# tester_V1_1.net
KiCad netlist of a schematic drawn in EAGLE
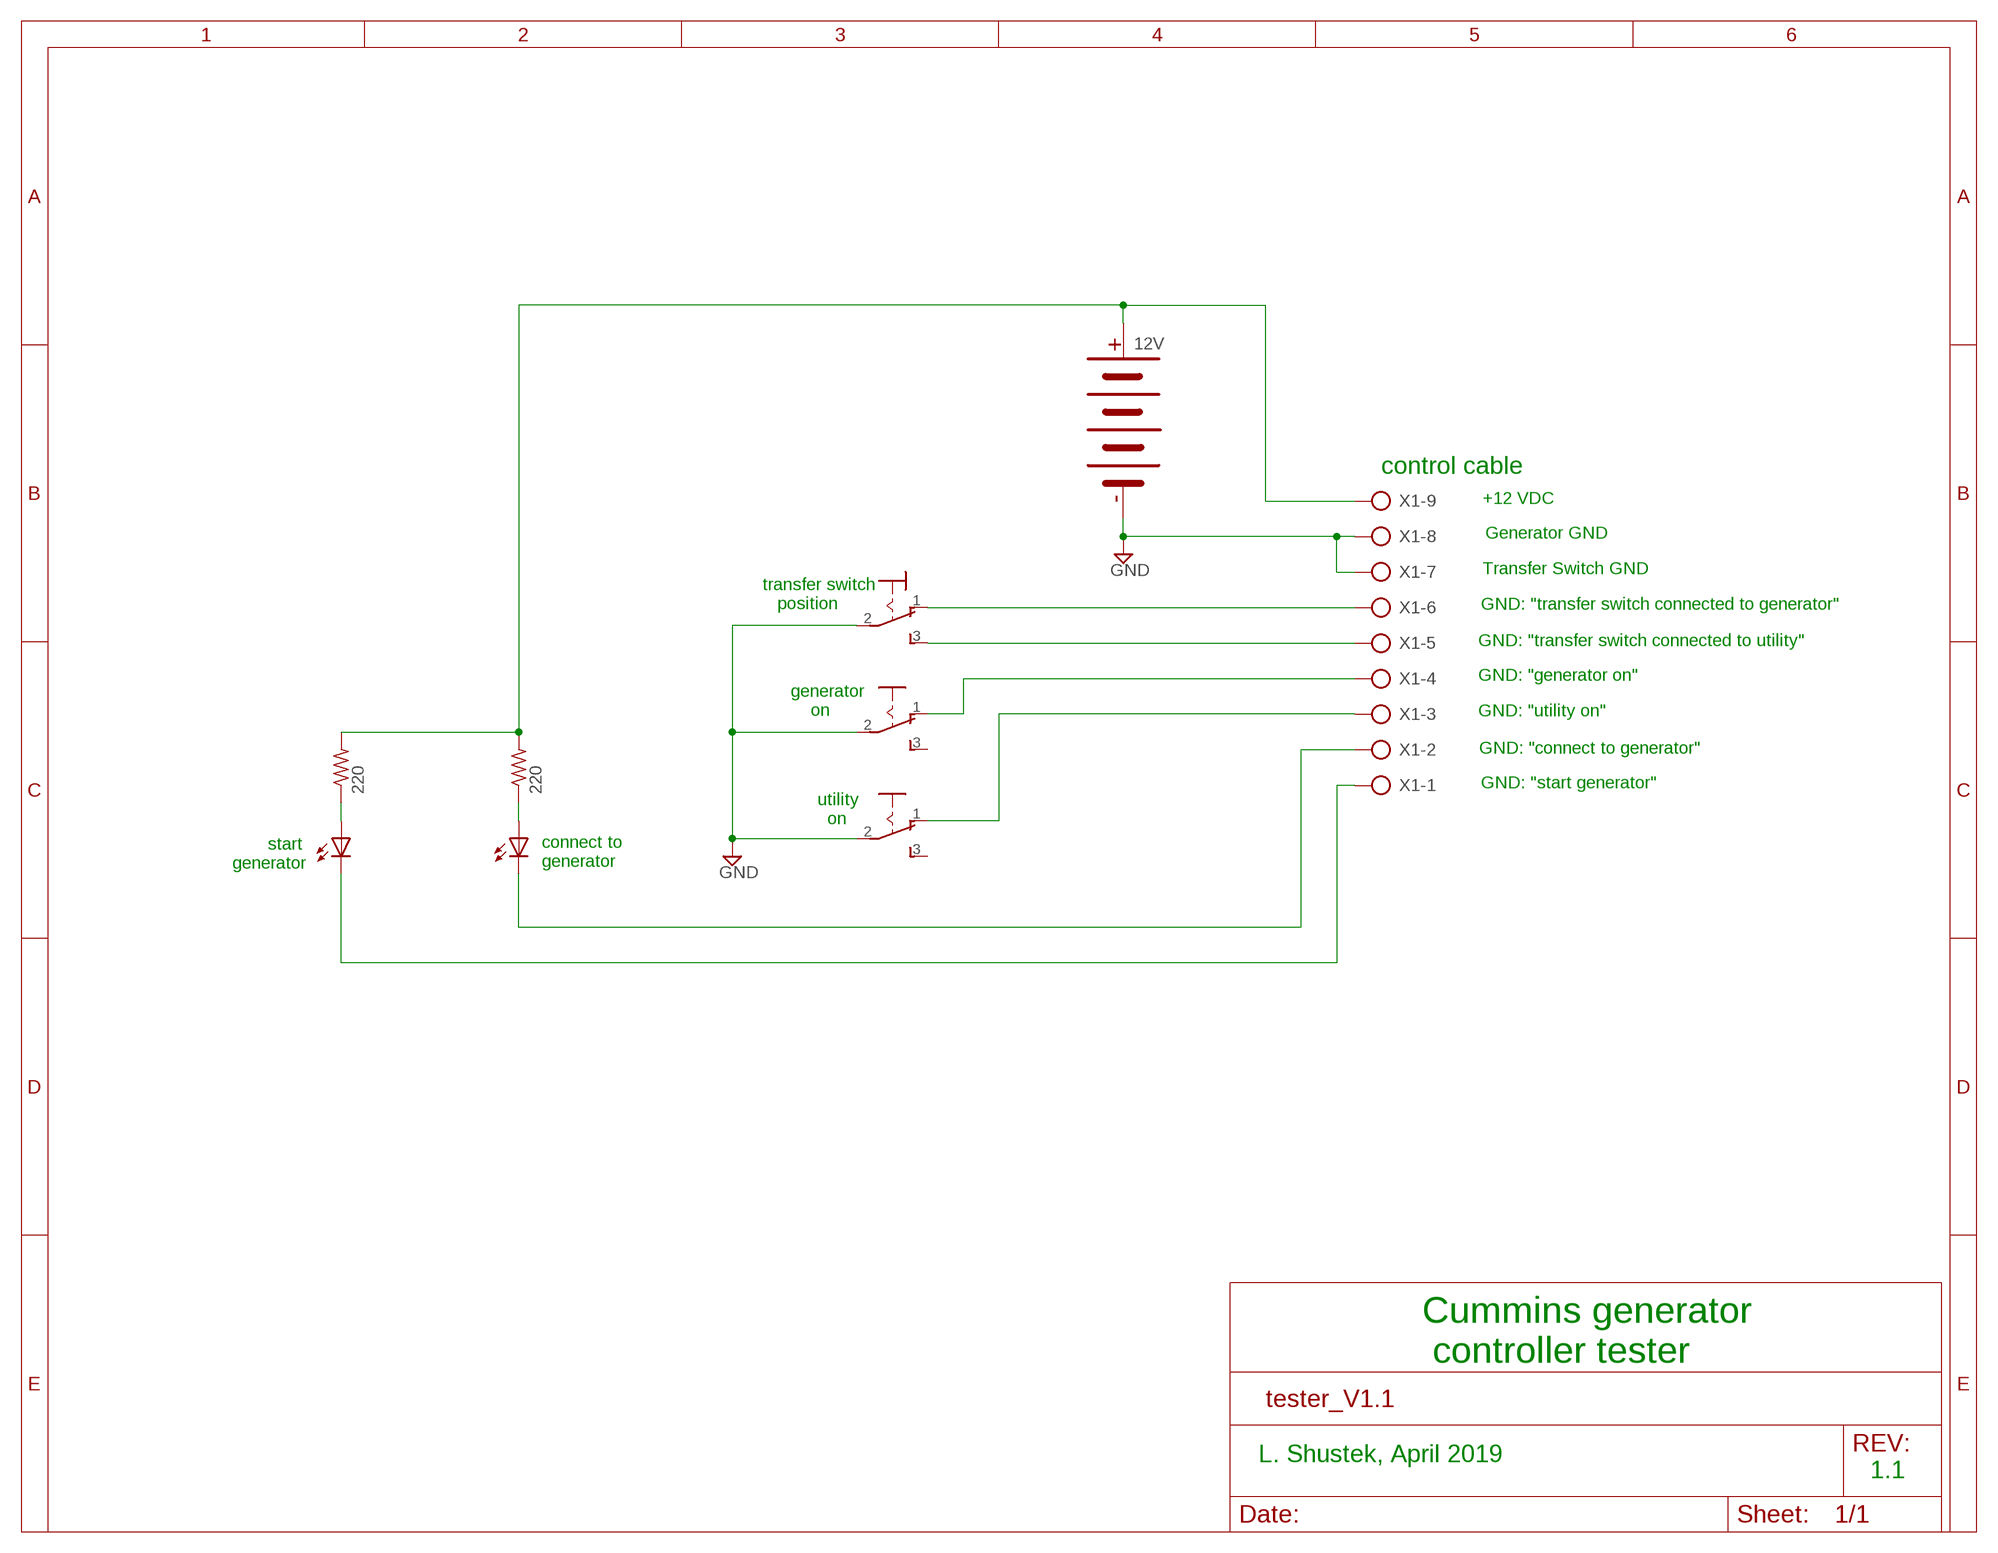
[diagram p0: schematic, sheet 1]

(export (version "E")
  (design (tool "Eeschema 10.0.6"))
  (components
    (comp (ref "LED1")
      (value "LED")
      (footprint "eagle-import:SMARTLED-TTW")
      (libsource (lib "eagle-import") (part "LED"))
    )
    (comp (ref "LED2")
      (value "LED")
      (footprint "eagle-import:SMARTLED-TTW")
      (libsource (lib "eagle-import") (part "LED"))
    )
    (comp (ref "R1")
      (value "220")
      (footprint "eagle-import:0204_5")
      (libsource (lib "eagle-import") (part "R-US_0204/5"))
    )
    (comp (ref "R2")
      (value "220")
      (footprint "eagle-import:0204_5")
      (libsource (lib "eagle-import") (part "R-US_0204/5"))
    )
    (comp (ref "S1")
      (value "320-916")
      (footprint "eagle-import:320-916")
      (libsource (lib "eagle-import") (part "320-916"))
    )
    (comp (ref "S2")
      (value "255SB")
      (footprint "eagle-import:255SB")
      (libsource (lib "eagle-import") (part "255SB"))
    )
    (comp (ref "S3")
      (value "255SB")
      (footprint "eagle-import:255SB")
      (libsource (lib "eagle-import") (part "255SB"))
    )
    (comp (ref "U$1")
      (value "12V")
      (footprint "eagle-import:4-CELL-BATTERY")
      (libsource (lib "eagle-import") (part "4-CELL-BATTERY"))
    )
    (comp (ref "X1")
      (value "AK500/9")
      (footprint "eagle-import:AK500_9")
      (libsource (lib "eagle-import") (part "AK500/9"))
    )
  )
  (nets
    (net (code "1") (name "GND") (class "Default")
      (node (ref "S1") (pin "2") (pinfunction "P_2") (pintype "passive"))
      (node (ref "S2") (pin "2") (pinfunction "P_2") (pintype "passive"))
      (node (ref "S3") (pin "2") (pinfunction "P_2") (pintype "passive"))
      (node (ref "U$1") (pin "P$1") (pinfunction "P$1_P$1") (pintype "bidirectional"))
      (node (ref "X1") (pin "7") (pinfunction "KL_7") (pintype "passive"))
      (node (ref "X1") (pin "8") (pinfunction "KL_8") (pintype "passive"))
    )
    (net (code "2") (name "Net-(LED1-A)") (class "Default")
      (node (ref "LED1") (pin "A@1") (pinfunction "A_A@1") (pintype "passive"))
      (node (ref "R1") (pin "1") (pinfunction "1_1") (pintype "passive"))
    )
    (net (code "3") (name "Net-(LED1-C)") (class "Default")
      (node (ref "LED1") (pin "C@1") (pinfunction "C_C@1") (pintype "passive"))
      (node (ref "X1") (pin "1") (pinfunction "KL_1") (pintype "passive"))
    )
    (net (code "4") (name "Net-(LED2-A)") (class "Default")
      (node (ref "LED2") (pin "A@1") (pinfunction "A_A@1") (pintype "passive"))
      (node (ref "R2") (pin "1") (pinfunction "1_1") (pintype "passive"))
    )
    (net (code "5") (name "Net-(LED2-C)") (class "Default")
      (node (ref "LED2") (pin "C@1") (pinfunction "C_C@1") (pintype "passive"))
      (node (ref "X1") (pin "2") (pinfunction "KL_2") (pintype "passive"))
    )
    (net (code "6") (name "Net-(S1-O)") (class "Default")
      (node (ref "S1") (pin "1") (pinfunction "O_1") (pintype "passive"))
      (node (ref "X1") (pin "6") (pinfunction "KL_6") (pintype "passive"))
    )
    (net (code "7") (name "Net-(S1-S)") (class "Default")
      (node (ref "S1") (pin "3") (pinfunction "S_3") (pintype "passive"))
      (node (ref "X1") (pin "5") (pinfunction "KL_5") (pintype "passive"))
    )
    (net (code "8") (name "Net-(S2-O)") (class "Default")
      (node (ref "S2") (pin "1") (pinfunction "O_1") (pintype "passive"))
      (node (ref "X1") (pin "4") (pinfunction "KL_4") (pintype "passive"))
    )
    (net (code "9") (name "Net-(S3-O)") (class "Default")
      (node (ref "S3") (pin "1") (pinfunction "O_1") (pintype "passive"))
      (node (ref "X1") (pin "3") (pinfunction "KL_3") (pintype "passive"))
    )
    (net (code "10") (name "Net-(X1I-KL)") (class "Default")
      (node (ref "R1") (pin "2") (pinfunction "2_2") (pintype "passive"))
      (node (ref "R2") (pin "2") (pinfunction "2_2") (pintype "passive"))
      (node (ref "U$1") (pin "P$2") (pinfunction "P$2_P$2") (pintype "bidirectional"))
      (node (ref "X1") (pin "9") (pinfunction "KL_9") (pintype "passive"))
    )
    (net (code "11") (name "unconnected-(S2-S-Pad3)") (class "Default")
      (node (ref "S2") (pin "3") (pinfunction "S_3") (pintype "passive"))
    )
    (net (code "12") (name "unconnected-(S3-S-Pad3)") (class "Default")
      (node (ref "S3") (pin "3") (pinfunction "S_3") (pintype "passive"))
    )
  )
)
